# AnalogueIsolatedReceiver.net
KiCad netlist of a schematic drawn in Altium Designer
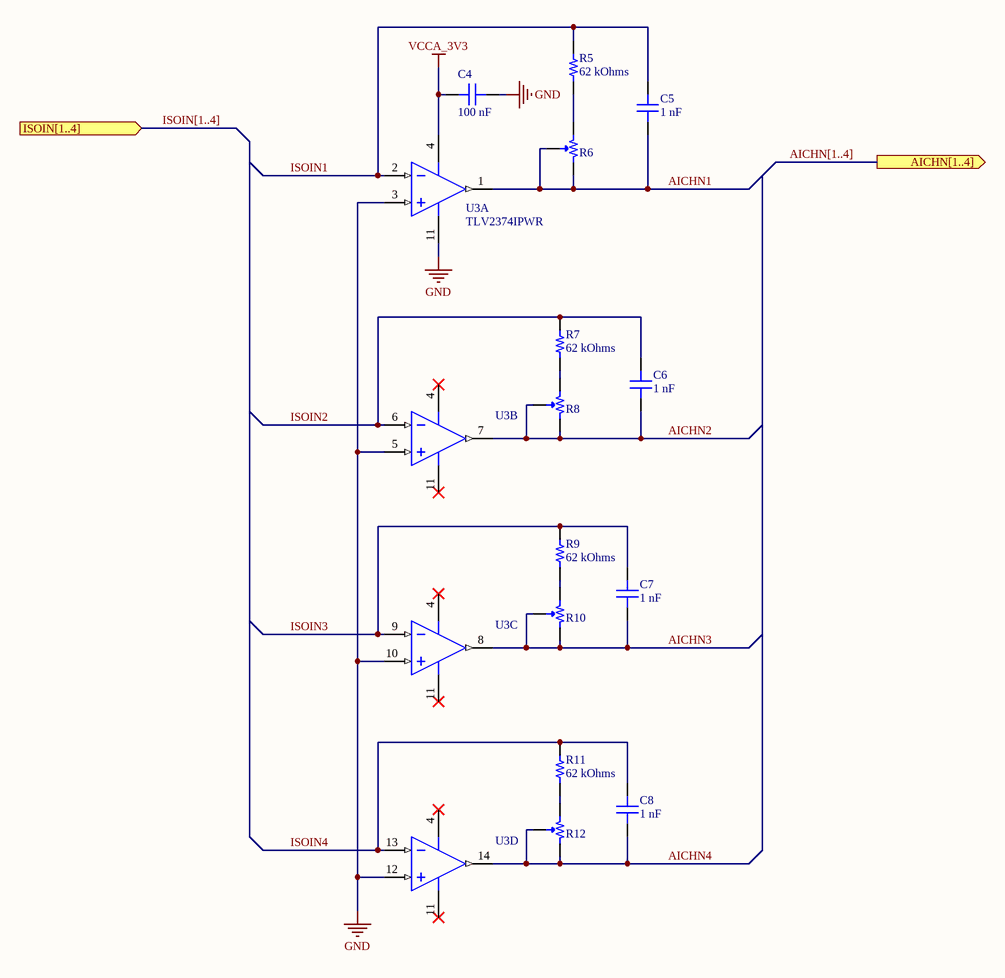
[diagram p0: AnalogueIsolatedReceiver.SchDoc]

(export (version "E")
  (design (tool "Eeschema 10.0.6"))
  (components
    (comp (ref "C4")
      (value "100 nF")
      (footprint "CAP 0603_1608")
      (description "MLCC Ceramic 100 nF 16 V 10% Capacitor")
      (fields (field (name "PART NUMBER") "0603YC104KAT2A") (field (name "MANUFACTURER") "AVX"))
      (libsource (lib "Database_Libs") (part "Capacitor"))
    )
    (comp (ref "C5")
      (value "1 nF")
      (footprint "CAP 0603_1608")
      (description "MLCC Ceramic 1 nF 10 V 5% Capacitor")
      (fields (field (name "PART NUMBER") "0603ZA102JAT4A") (field (name "MANUFACTURER") "AVX"))
      (libsource (lib "Database_Libs") (part "Capacitor"))
    )
    (comp (ref "C6")
      (value "1 nF")
      (footprint "CAP 0603_1608")
      (description "MLCC Ceramic 1 nF 10 V 5% Capacitor")
      (fields (field (name "PART NUMBER") "0603ZA102JAT4A") (field (name "MANUFACTURER") "AVX"))
      (libsource (lib "Database_Libs") (part "Capacitor"))
    )
    (comp (ref "C7")
      (value "1 nF")
      (footprint "CAP 0603_1608")
      (description "MLCC Ceramic 1 nF 10 V 5% Capacitor")
      (fields (field (name "PART NUMBER") "0603ZA102JAT4A") (field (name "MANUFACTURER") "AVX"))
      (libsource (lib "Database_Libs") (part "Capacitor"))
    )
    (comp (ref "C8")
      (value "1 nF")
      (footprint "CAP 0603_1608")
      (description "MLCC Ceramic 1 nF 10 V 5% Capacitor")
      (fields (field (name "PART NUMBER") "0603ZA102JAT4A") (field (name "MANUFACTURER") "AVX"))
      (libsource (lib "Database_Libs") (part "Capacitor"))
    )
    (comp (ref "R5")
      (value "62 kOhms")
      (footprint "RES 0603_1608")
      (description "Thin Film Resistor 62 kOhms 1%")
      (fields (field (name "PART NUMBER") "CRCW060362K0FKEAC") (field (name "MANUFACTURER") "Vishay / Dale"))
      (libsource (lib "Database_Libs") (part "Resistor"))
    )
    (comp (ref "R6")
      (value "10 kOhms")
      (footprint "POT BOURNS TRIMPOT 3224W")
      (description "Inline Multitourn 10 kOhms 10% potentiometer")
      (fields (field (name "PART NUMBER") "3224W-1-103G") (field (name "MANUFACTURER") "Bourns"))
      (libsource (lib "Database_Libs") (part "Potentiometer"))
    )
    (comp (ref "R7")
      (value "62 kOhms")
      (footprint "RES 0603_1608")
      (description "Thin Film Resistor 62 kOhms 1%")
      (fields (field (name "PART NUMBER") "CRCW060362K0FKEAC") (field (name "MANUFACTURER") "Vishay / Dale"))
      (libsource (lib "Database_Libs") (part "Resistor"))
    )
    (comp (ref "R8")
      (value "10 kOhms")
      (footprint "POT BOURNS TRIMPOT 3224W")
      (description "Inline Multitourn 10 kOhms 10% potentiometer")
      (fields (field (name "PART NUMBER") "3224W-1-103G") (field (name "MANUFACTURER") "Bourns"))
      (libsource (lib "Database_Libs") (part "Potentiometer"))
    )
    (comp (ref "R9")
      (value "62 kOhms")
      (footprint "RES 0603_1608")
      (description "Thin Film Resistor 62 kOhms 1%")
      (fields (field (name "PART NUMBER") "CRCW060362K0FKEAC") (field (name "MANUFACTURER") "Vishay / Dale"))
      (libsource (lib "Database_Libs") (part "Resistor"))
    )
    (comp (ref "R10")
      (value "10 kOhms")
      (footprint "POT BOURNS TRIMPOT 3224W")
      (description "Inline Multitourn 10 kOhms 10% potentiometer")
      (fields (field (name "PART NUMBER") "3224W-1-103G") (field (name "MANUFACTURER") "Bourns"))
      (libsource (lib "Database_Libs") (part "Potentiometer"))
    )
    (comp (ref "R11")
      (value "62 kOhms")
      (footprint "RES 0603_1608")
      (description "Thin Film Resistor 62 kOhms 1%")
      (fields (field (name "PART NUMBER") "CRCW060362K0FKEAC") (field (name "MANUFACTURER") "Vishay / Dale"))
      (libsource (lib "Database_Libs") (part "Resistor"))
    )
    (comp (ref "R12")
      (value "10 kOhms")
      (footprint "POT BOURNS TRIMPOT 3224W")
      (description "Inline Multitourn 10 kOhms 10% potentiometer")
      (fields (field (name "PART NUMBER") "3224W-1-103G") (field (name "MANUFACTURER") "Bourns"))
      (libsource (lib "Database_Libs") (part "Potentiometer"))
    )
    (comp (ref "U3")
      (value "TLV2374IPWR")
      (footprint "TI TSSOP-14 PW")
      (description "TLV2374 Rail-to-Rail I/O Opamp")
      (fields (field (name "MANUFACTURER") "Texas Instruments"))
      (libsource (lib "Database_Libs") (part "TLV2374"))
    )
  )
  (nets
    (net (code "1") (name "/AICHN1") (class "Default")
      (node (ref "C5") (pin "2") (pinfunction "2_2") (pintype "passive"))
      (node (ref "R6") (pin "2") (pinfunction "2_2") (pintype "passive"))
      (node (ref "R6") (pin "3") (pinfunction "3_3") (pintype "passive"))
      (node (ref "U3") (pin "1") (pinfunction "OUT1_1") (pintype "output"))
    )
    (net (code "2") (name "/AICHN2") (class "Default")
      (node (ref "C6") (pin "2") (pinfunction "2_2") (pintype "passive"))
      (node (ref "R8") (pin "2") (pinfunction "2_2") (pintype "passive"))
      (node (ref "R8") (pin "3") (pinfunction "3_3") (pintype "passive"))
      (node (ref "U3") (pin "7") (pinfunction "OUT2_7") (pintype "output"))
    )
    (net (code "3") (name "/AICHN3") (class "Default")
      (node (ref "C7") (pin "2") (pinfunction "2_2") (pintype "passive"))
      (node (ref "R10") (pin "2") (pinfunction "2_2") (pintype "passive"))
      (node (ref "R10") (pin "3") (pinfunction "3_3") (pintype "passive"))
      (node (ref "U3") (pin "8") (pinfunction "OUT3_8") (pintype "output"))
    )
    (net (code "4") (name "/AICHN4") (class "Default")
      (node (ref "C8") (pin "2") (pinfunction "2_2") (pintype "passive"))
      (node (ref "R12") (pin "2") (pinfunction "2_2") (pintype "passive"))
      (node (ref "R12") (pin "3") (pinfunction "3_3") (pintype "passive"))
      (node (ref "U3") (pin "14") (pinfunction "OUT4_14") (pintype "output"))
    )
    (net (code "6") (name "/ISOIN1") (class "Default")
      (node (ref "C5") (pin "1") (pinfunction "1_1") (pintype "passive"))
      (node (ref "R5") (pin "2") (pinfunction "2_2") (pintype "passive"))
      (node (ref "U3") (pin "2") (pinfunction "IN1-_2") (pintype "input"))
    )
    (net (code "7") (name "/ISOIN2") (class "Default")
      (node (ref "C6") (pin "1") (pinfunction "1_1") (pintype "passive"))
      (node (ref "R7") (pin "2") (pinfunction "2_2") (pintype "passive"))
      (node (ref "U3") (pin "6") (pinfunction "IN2-_6") (pintype "input"))
    )
    (net (code "8") (name "/ISOIN3") (class "Default")
      (node (ref "C7") (pin "1") (pinfunction "1_1") (pintype "passive"))
      (node (ref "R9") (pin "2") (pinfunction "2_2") (pintype "passive"))
      (node (ref "U3") (pin "9") (pinfunction "IN3-_9") (pintype "input"))
    )
    (net (code "9") (name "/ISOIN4") (class "Default")
      (node (ref "C8") (pin "1") (pinfunction "1_1") (pintype "passive"))
      (node (ref "R11") (pin "2") (pinfunction "2_2") (pintype "passive"))
      (node (ref "U3") (pin "13") (pinfunction "IN4-_13") (pintype "input"))
    )
    (net (code "11") (name "GND") (class "Default")
      (node (ref "C4") (pin "1") (pinfunction "1_1") (pintype "passive"))
      (node (ref "U3") (pin "10") (pinfunction "IN3+_10") (pintype "input"))
      (node (ref "U3") (pin "11") (pinfunction "GND_11") (pintype "power_in"))
      (node (ref "U3") (pin "12") (pinfunction "IN4+_12") (pintype "input"))
      (node (ref "U3") (pin "3") (pinfunction "IN1+_3") (pintype "input"))
      (node (ref "U3") (pin "5") (pinfunction "IN2+_5") (pintype "input"))
    )
    (net (code "12") (name "Net-(R5-Pad1)") (class "Default")
      (node (ref "R5") (pin "1") (pinfunction "1_1") (pintype "passive"))
      (node (ref "R6") (pin "1") (pinfunction "1_1") (pintype "passive"))
    )
    (net (code "13") (name "Net-(R7-Pad1)") (class "Default")
      (node (ref "R7") (pin "1") (pinfunction "1_1") (pintype "passive"))
      (node (ref "R8") (pin "1") (pinfunction "1_1") (pintype "passive"))
    )
    (net (code "14") (name "Net-(R10-Pad1)") (class "Default")
      (node (ref "R10") (pin "1") (pinfunction "1_1") (pintype "passive"))
      (node (ref "R9") (pin "1") (pinfunction "1_1") (pintype "passive"))
    )
    (net (code "15") (name "Net-(R11-Pad1)") (class "Default")
      (node (ref "R11") (pin "1") (pinfunction "1_1") (pintype "passive"))
      (node (ref "R12") (pin "1") (pinfunction "1_1") (pintype "passive"))
    )
    (net (code "16") (name "VCCA_3V3") (class "Default")
      (node (ref "C4") (pin "2") (pinfunction "2_2") (pintype "passive"))
      (node (ref "U3") (pin "4") (pinfunction "VDD_4") (pintype "power_in"))
    )
    (net (code "17") (name "unconnected-(U3B-GND-Pad11)") (class "Default")
      (node (ref "U3") (pin "11") (pinfunction "GND_11") (pintype "power_in+no_connect"))
    )
    (net (code "18") (name "unconnected-(U3B-VDD-Pad4)") (class "Default")
      (node (ref "U3") (pin "4") (pinfunction "VDD_4") (pintype "power_in+no_connect"))
    )
    (net (code "19") (name "unconnected-(U3C-GND-Pad11)") (class "Default")
      (node (ref "U3") (pin "11") (pinfunction "GND_11") (pintype "power_in+no_connect"))
    )
    (net (code "20") (name "unconnected-(U3C-VDD-Pad4)") (class "Default")
      (node (ref "U3") (pin "4") (pinfunction "VDD_4") (pintype "power_in+no_connect"))
    )
    (net (code "21") (name "unconnected-(U3D-GND-Pad11)") (class "Default")
      (node (ref "U3") (pin "11") (pinfunction "GND_11") (pintype "power_in+no_connect"))
    )
    (net (code "22") (name "unconnected-(U3D-VDD-Pad4)") (class "Default")
      (node (ref "U3") (pin "4") (pinfunction "VDD_4") (pintype "power_in+no_connect"))
    )
  )
)
